# Un_Bus_A.net
KiCad netlist of a schematic drawn in EAGLE
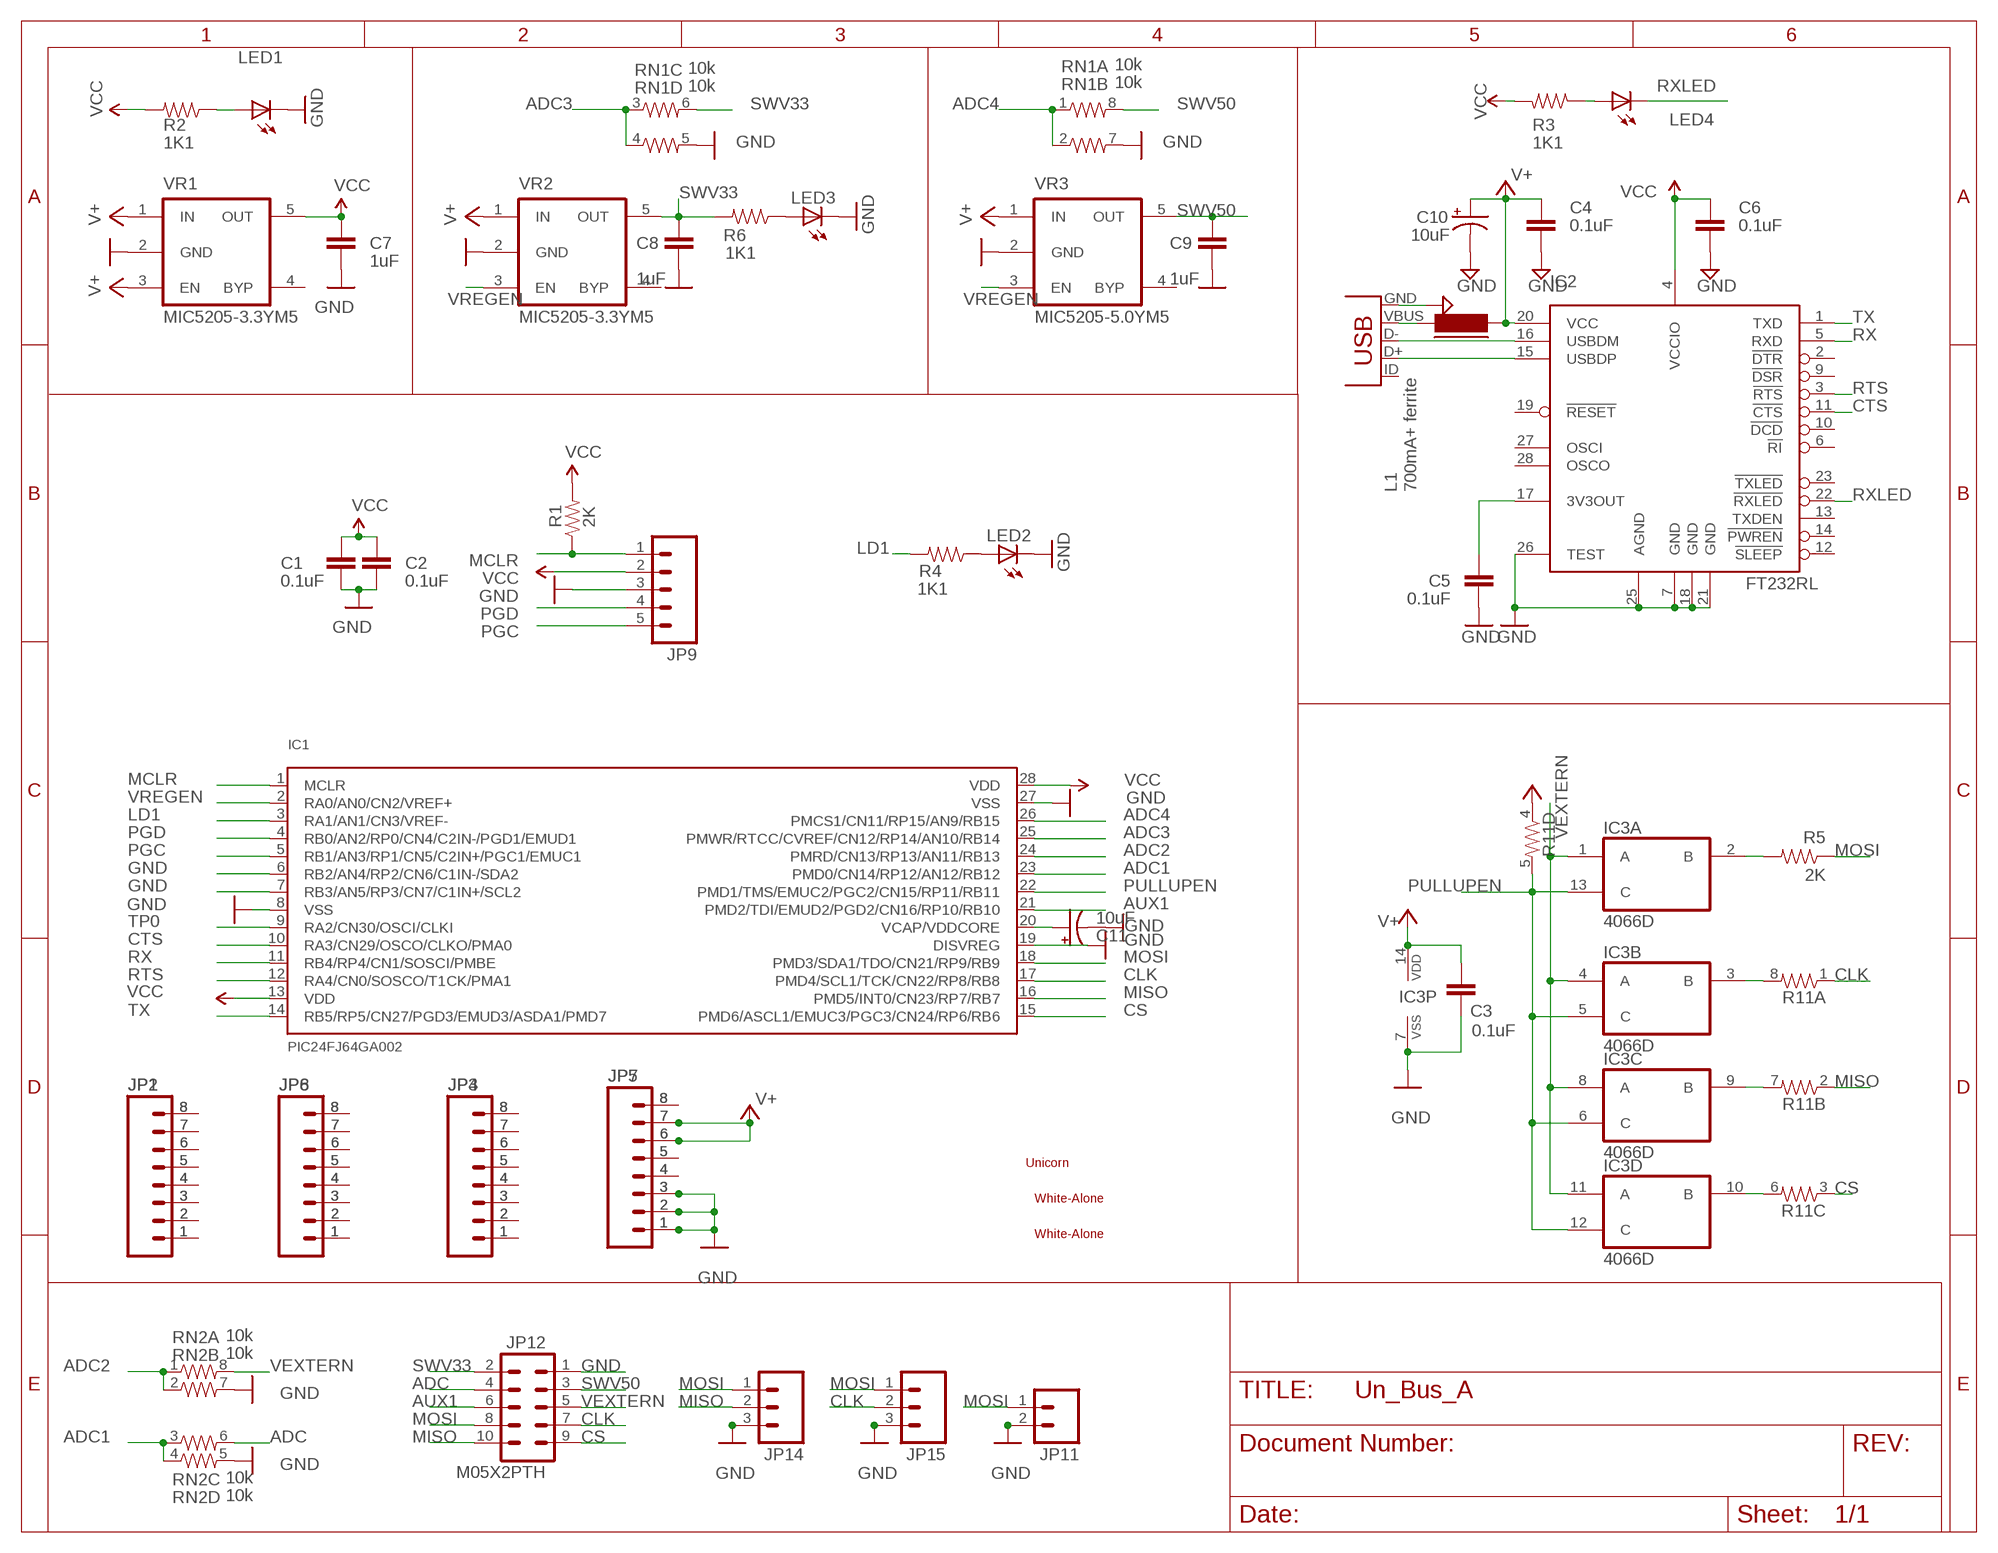
[diagram p0: schematic, sheet 1]

(export (version "E")
  (design (tool "Eeschema 10.0.6"))
  (components
    (comp (ref "C1")
      (value "0.1uF")
      (footprint "eagle-import:0603-CAP")
      (libsource (lib "eagle-import") (part "CAP0603-CAP"))
    )
    (comp (ref "C2")
      (value "0.1uF")
      (footprint "eagle-import:0603-CAP")
      (libsource (lib "eagle-import") (part "CAP0603-CAP"))
    )
    (comp (ref "C3")
      (value "0.1uF")
      (footprint "eagle-import:0603-CAP")
      (libsource (lib "eagle-import") (part "CAP0603-CAP"))
    )
    (comp (ref "C4")
      (value "0.1uF")
      (footprint "eagle-import:0603-CAP")
      (libsource (lib "eagle-import") (part "CAP0603-CAP"))
    )
    (comp (ref "C5")
      (value "0.1uF")
      (footprint "eagle-import:0603-CAP")
      (libsource (lib "eagle-import") (part "CAP0603-CAP"))
    )
    (comp (ref "C6")
      (value "0.1uF")
      (footprint "eagle-import:0603-CAP")
      (libsource (lib "eagle-import") (part "CAP0603-CAP"))
    )
    (comp (ref "C7")
      (value "1uF")
      (footprint "eagle-import:0603-CAP")
      (libsource (lib "eagle-import") (part "CAP0603-CAP"))
    )
    (comp (ref "C8")
      (value "1uF")
      (footprint "eagle-import:0603-CAP")
      (libsource (lib "eagle-import") (part "CAP0603-CAP"))
    )
    (comp (ref "C9")
      (value "1uF")
      (footprint "eagle-import:0603-CAP")
      (libsource (lib "eagle-import") (part "CAP0603-CAP"))
    )
    (comp (ref "C10")
      (value "10uF")
      (footprint "eagle-import:EIA3216")
      (libsource (lib "eagle-import") (part "CAP_POL1206"))
    )
    (comp (ref "C11")
      (value "10uF")
      (footprint "eagle-import:EIA3216")
      (libsource (lib "eagle-import") (part "CAP_POL1206"))
    )
    (comp (ref "IC1")
      (value "PIC24FJ64GA002")
      (footprint "eagle-import:SSOP28")
      (libsource (lib "eagle-import") (part "PIC24FJ64GA002"))
    )
    (comp (ref "IC2")
      (value "FT232RL")
      (footprint "eagle-import:SSOP28")
      (libsource (lib "eagle-import") (part "FT232RL"))
    )
    (comp (ref "IC3")
      (value "4066D")
      (footprint "eagle-import:SO14")
      (libsource (lib "eagle-import") (part "4066D"))
    )
    (comp (ref "JP1")
      (value "M081X08")
      (footprint "eagle-import:1X08")
      (libsource (lib "eagle-import") (part "M081X08"))
    )
    (comp (ref "JP2")
      (value "M081X08")
      (footprint "eagle-import:1X08")
      (libsource (lib "eagle-import") (part "M081X08"))
    )
    (comp (ref "JP3")
      (value "M081X08")
      (footprint "eagle-import:1X08")
      (libsource (lib "eagle-import") (part "M081X08"))
    )
    (comp (ref "JP4")
      (value "M081X08")
      (footprint "eagle-import:1X08")
      (libsource (lib "eagle-import") (part "M081X08"))
    )
    (comp (ref "JP5")
      (value "M081X08")
      (footprint "eagle-import:1X08")
      (libsource (lib "eagle-import") (part "M081X08"))
    )
    (comp (ref "JP6")
      (value "M081X08")
      (footprint "eagle-import:1X08")
      (libsource (lib "eagle-import") (part "M081X08"))
    )
    (comp (ref "JP7")
      (value "M081X08")
      (footprint "eagle-import:1X08")
      (libsource (lib "eagle-import") (part "M081X08"))
    )
    (comp (ref "JP8")
      (value "M081X08")
      (footprint "eagle-import:1X08")
      (libsource (lib "eagle-import") (part "M081X08"))
    )
    (comp (ref "JP9")
      (value "M05PTH")
      (footprint "eagle-import:1X05")
      (libsource (lib "eagle-import") (part "M05PTH"))
    )
    (comp (ref "JP11")
      (value "M02PTH")
      (footprint "eagle-import:1X02")
      (libsource (lib "eagle-import") (part "M02PTH"))
    )
    (comp (ref "JP12")
      (value "M05X2PTH")
      (footprint "eagle-import:AVR_ICSP")
      (libsource (lib "eagle-import") (part "M05X2PTH"))
    )
    (comp (ref "JP14")
      (value "M03PTH")
      (footprint "eagle-import:1X03")
      (libsource (lib "eagle-import") (part "M03PTH"))
    )
    (comp (ref "JP15")
      (value "M03PTH")
      (footprint "eagle-import:1X03")
      (libsource (lib "eagle-import") (part "M03PTH"))
    )
    (comp (ref "L1")
      (value "700mA+ ferrite")
      (footprint "eagle-import:FB805")
      (libsource (lib "eagle-import") (part "FERRITE-0805"))
    )
    (comp (ref "LED1")
      (value "LED0805")
      (footprint "eagle-import:LED-0805")
      (libsource (lib "eagle-import") (part "LED0805"))
    )
    (comp (ref "LED2")
      (value "LED0805")
      (footprint "eagle-import:LED-0805")
      (libsource (lib "eagle-import") (part "LED0805"))
    )
    (comp (ref "LED3")
      (value "LED0805")
      (footprint "eagle-import:LED-0805")
      (libsource (lib "eagle-import") (part "LED0805"))
    )
    (comp (ref "LED4")
      (value "LED0805")
      (footprint "eagle-import:LED-0805")
      (libsource (lib "eagle-import") (part "LED0805"))
    )
    (comp (ref "R1")
      (value "2K")
      (footprint "eagle-import:0603-RES")
      (libsource (lib "eagle-import") (part "2SparkFun_RESISTOR0603-RES"))
    )
    (comp (ref "R2")
      (value "1K1")
      (footprint "eagle-import:0603-RES")
      (libsource (lib "eagle-import") (part "RESISTOR0603-RES"))
    )
    (comp (ref "R3")
      (value "1K1")
      (footprint "eagle-import:0603-RES")
      (libsource (lib "eagle-import") (part "RESISTOR0603-RES"))
    )
    (comp (ref "R4")
      (value "1K1")
      (footprint "eagle-import:0603-RES")
      (libsource (lib "eagle-import") (part "RESISTOR0603-RES"))
    )
    (comp (ref "R5")
      (value "2K")
      (footprint "eagle-import:0603-RES")
      (libsource (lib "eagle-import") (part "2SparkFun_RESISTOR0603-RES"))
    )
    (comp (ref "R6")
      (value "1K1")
      (footprint "eagle-import:0603-RES")
      (libsource (lib "eagle-import") (part "RESISTOR0603-RES"))
    )
    (comp (ref "R11")
      (value "RESISTOR-ARRAY")
      (footprint "eagle-import:RES-NET-0603")
      (libsource (lib "eagle-import") (part "RESISTOR-ARRAY"))
    )
    (comp (ref "RN1")
      (value "10k")
      (footprint "eagle-import:RES-NET-0603")
      (libsource (lib "eagle-import") (part "RESISTOR-ARRAY"))
    )
    (comp (ref "RN2")
      (value "10k")
      (footprint "eagle-import:RES-NET-0603")
      (libsource (lib "eagle-import") (part "RESISTOR-ARRAY"))
    )
    (comp (ref "U$1")
      (value "UNICORN")
      (footprint "eagle-import:UNICORN_1")
      (libsource (lib "eagle-import") (part "UNICORN"))
    )
    (comp (ref "U$2")
      (value "WHITE-ALONE_0")
      (footprint "eagle-import:WHITE-ALONE_0")
      (libsource (lib "eagle-import") (part "WHITE-ALONE_0"))
    )
    (comp (ref "U$3")
      (value "WHITE-ALONE_0")
      (footprint "eagle-import:WHITE-ALONE_0")
      (libsource (lib "eagle-import") (part "WHITE-ALONE_0"))
    )
    (comp (ref "VR1")
      (value "MIC5205-3.3YM5")
      (footprint "eagle-import:SOT-23-5")
      (libsource (lib "eagle-import") (part "MIC5205"))
    )
    (comp (ref "VR2")
      (value "MIC5205-3.3YM5")
      (footprint "eagle-import:SOT-23-5")
      (libsource (lib "eagle-import") (part "MIC5205"))
    )
    (comp (ref "VR3")
      (value "MIC5205-5.0YM5")
      (footprint "eagle-import:SOT-23-5")
      (libsource (lib "eagle-import") (part "MIC5205"))
    )
    (comp (ref "X1")
      (value "USBSMD")
      (footprint "eagle-import:USB-MINIB")
      (libsource (lib "eagle-import") (part "USBSMD"))
    )
  )
  (nets
    (net (code "1") (name "/ADC") (class "Default")
      (node (ref "JP12") (pin "4") (pinfunction "4_4") (pintype "passive"))
      (node (ref "RN2") (pin "6") (pinfunction "2_6") (pintype "passive"))
    )
    (net (code "2") (name "/ADC1") (class "Default")
      (node (ref "IC1") (pin "23") (pinfunction "PMD0/CN14/RP12/AN12/RB12_23") (pintype "bidirectional"))
      (node (ref "RN2") (pin "3") (pinfunction "1_3") (pintype "passive"))
      (node (ref "RN2") (pin "4") (pinfunction "1_4") (pintype "passive"))
    )
    (net (code "3") (name "/ADC2") (class "Default")
      (node (ref "IC1") (pin "24") (pinfunction "PMRD/CN13/RP13/AN11/RB13_24") (pintype "bidirectional"))
      (node (ref "RN2") (pin "1") (pinfunction "1_1") (pintype "passive"))
      (node (ref "RN2") (pin "2") (pinfunction "1_2") (pintype "passive"))
    )
    (net (code "4") (name "/ADC3") (class "Default")
      (node (ref "IC1") (pin "25") (pinfunction "PMWR/RTCC/CVREF/CN12/RP14/AN10/RB14_25") (pintype "bidirectional"))
      (node (ref "RN1") (pin "3") (pinfunction "1_3") (pintype "passive"))
      (node (ref "RN1") (pin "4") (pinfunction "1_4") (pintype "passive"))
    )
    (net (code "5") (name "/ADC4") (class "Default")
      (node (ref "IC1") (pin "26") (pinfunction "PMCS1/CN11/RP15/AN9/RB15_26") (pintype "bidirectional"))
      (node (ref "RN1") (pin "1") (pinfunction "1_1") (pintype "passive"))
      (node (ref "RN1") (pin "2") (pinfunction "1_2") (pintype "passive"))
    )
    (net (code "6") (name "/AUX1") (class "Default")
      (node (ref "IC1") (pin "21") (pinfunction "PMD2/TDI/EMUD2/PGD2/CN16/RP10/RB10_21") (pintype "bidirectional"))
      (node (ref "JP12") (pin "6") (pinfunction "6_6") (pintype "passive"))
    )
    (net (code "7") (name "/CLK") (class "Default")
      (node (ref "IC1") (pin "17") (pinfunction "PMD4/SCL1/TCK/CN22/RP8/RB8_17") (pintype "bidirectional"))
      (node (ref "JP12") (pin "7") (pinfunction "7_7") (pintype "passive"))
      (node (ref "JP15") (pin "2") (pinfunction "2_2") (pintype "passive"))
      (node (ref "R11") (pin "1") (pinfunction "1_1") (pintype "passive"))
    )
    (net (code "8") (name "/CS") (class "Default")
      (node (ref "IC1") (pin "15") (pinfunction "PMD6/ASCL1/EMUC3/PGC3/CN24/RP6/RB6_15") (pintype "bidirectional"))
      (node (ref "JP12") (pin "9") (pinfunction "9_9") (pintype "passive"))
      (node (ref "R11") (pin "3") (pinfunction "1_3") (pintype "passive"))
    )
    (net (code "9") (name "/CTS") (class "Default")
      (node (ref "IC1") (pin "10") (pinfunction "RA3/CN29/OSCO/CLKO/PMA0_10") (pintype "bidirectional"))
      (node (ref "IC2") (pin "11") (pinfunction "~{CTS}_11") (pintype "bidirectional"))
    )
    (net (code "10") (name "/LD1") (class "Default")
      (node (ref "IC1") (pin "3") (pinfunction "RA1/AN1/CN3/VREF-_3") (pintype "bidirectional"))
      (node (ref "R4") (pin "2") (pinfunction "2_2") (pintype "passive"))
    )
    (net (code "11") (name "/MCLR") (class "Default")
      (node (ref "IC1") (pin "1") (pinfunction "MCLR_1") (pintype "input"))
      (node (ref "JP9") (pin "1") (pinfunction "1_1") (pintype "passive"))
      (node (ref "R1") (pin "1") (pinfunction "1_1") (pintype "passive"))
    )
    (net (code "12") (name "/MISO") (class "Default")
      (node (ref "IC1") (pin "16") (pinfunction "PMD5/INT0/CN23/RP7/RB7_16") (pintype "bidirectional"))
      (node (ref "JP12") (pin "10") (pinfunction "10_10") (pintype "passive"))
      (node (ref "JP14") (pin "2") (pinfunction "2_2") (pintype "passive"))
      (node (ref "R11") (pin "2") (pinfunction "1_2") (pintype "passive"))
    )
    (net (code "13") (name "/MOSI") (class "Default")
      (node (ref "IC1") (pin "18") (pinfunction "PMD3/SDA1/TDO/CN21/RP9/RB9_18") (pintype "bidirectional"))
      (node (ref "JP11") (pin "1") (pinfunction "1_1") (pintype "passive"))
      (node (ref "JP12") (pin "8") (pinfunction "8_8") (pintype "passive"))
      (node (ref "JP14") (pin "1") (pinfunction "1_1") (pintype "passive"))
      (node (ref "JP15") (pin "1") (pinfunction "1_1") (pintype "passive"))
      (node (ref "R5") (pin "1") (pinfunction "1_1") (pintype "passive"))
    )
    (net (code "14") (name "/PGC") (class "Default")
      (node (ref "IC1") (pin "5") (pinfunction "RB1/AN3/RP1/CN5/C2IN+/PGC1/EMUC1_5") (pintype "bidirectional"))
      (node (ref "JP9") (pin "5") (pinfunction "5_5") (pintype "passive"))
    )
    (net (code "15") (name "/PGD") (class "Default")
      (node (ref "IC1") (pin "4") (pinfunction "RB0/AN2/RP0/CN4/C2IN-/PGD1/EMUD1_4") (pintype "bidirectional"))
      (node (ref "JP9") (pin "4") (pinfunction "4_4") (pintype "passive"))
    )
    (net (code "16") (name "/PULLUPEN") (class "Default")
      (node (ref "IC1") (pin "22") (pinfunction "PMD1/TMS/EMUC2/PGC2/CN15/RP11/RB11_22") (pintype "bidirectional"))
      (node (ref "IC3") (pin "12") (pinfunction "C_12") (pintype "input"))
      (node (ref "IC3") (pin "13") (pinfunction "C_13") (pintype "input"))
      (node (ref "IC3") (pin "5") (pinfunction "C_5") (pintype "input"))
      (node (ref "IC3") (pin "6") (pinfunction "C_6") (pintype "input"))
      (node (ref "R11") (pin "5") (pinfunction "2_5") (pintype "passive"))
    )
    (net (code "17") (name "/RTS") (class "Default")
      (node (ref "IC1") (pin "12") (pinfunction "RA4/CN0/SOSCO/T1CK/PMA1_12") (pintype "bidirectional"))
      (node (ref "IC2") (pin "3") (pinfunction "~{RTS}_3") (pintype "bidirectional"))
    )
    (net (code "18") (name "/RX") (class "Default")
      (node (ref "IC1") (pin "11") (pinfunction "RB4/RP4/CN1/SOSCI/PMBE_11") (pintype "bidirectional"))
      (node (ref "IC2") (pin "5") (pinfunction "RXD_5") (pintype "bidirectional"))
    )
    (net (code "19") (name "/RXLED") (class "Default")
      (node (ref "IC2") (pin "22") (pinfunction "~{RXLED}_22") (pintype "bidirectional"))
      (node (ref "LED4") (pin "2") (pinfunction "C_2") (pintype "passive"))
    )
    (net (code "20") (name "/SWV33") (class "Default")
      (node (ref "C8") (pin "1") (pinfunction "1_1") (pintype "passive"))
      (node (ref "JP12") (pin "2") (pinfunction "2_2") (pintype "passive"))
      (node (ref "R6") (pin "2") (pinfunction "2_2") (pintype "passive"))
      (node (ref "RN1") (pin "6") (pinfunction "2_6") (pintype "passive"))
      (node (ref "VR2") (pin "5") (pinfunction "OUT_5") (pintype "bidirectional"))
    )
    (net (code "21") (name "/SWV50") (class "Default")
      (node (ref "C9") (pin "1") (pinfunction "1_1") (pintype "passive"))
      (node (ref "JP12") (pin "3") (pinfunction "3_3") (pintype "passive"))
      (node (ref "RN1") (pin "8") (pinfunction "2_8") (pintype "passive"))
      (node (ref "VR3") (pin "5") (pinfunction "OUT_5") (pintype "bidirectional"))
    )
    (net (code "22") (name "/TP0") (class "Default")
      (node (ref "IC1") (pin "9") (pinfunction "RA2/CN30/OSCI/CLKI_9") (pintype "bidirectional"))
    )
    (net (code "23") (name "/TX") (class "Default")
      (node (ref "IC1") (pin "14") (pinfunction "RB5/RP5/CN27/PGD3/EMUD3/ASDA1/PMD7_14") (pintype "bidirectional"))
      (node (ref "IC2") (pin "1") (pinfunction "TXD_1") (pintype "bidirectional"))
    )
    (net (code "24") (name "/VEXTERN") (class "Default")
      (node (ref "IC3") (pin "1") (pinfunction "A_1") (pintype "tri_state"))
      (node (ref "IC3") (pin "11") (pinfunction "A_11") (pintype "tri_state"))
      (node (ref "IC3") (pin "4") (pinfunction "A_4") (pintype "tri_state"))
      (node (ref "IC3") (pin "8") (pinfunction "A_8") (pintype "tri_state"))
      (node (ref "JP12") (pin "5") (pinfunction "5_5") (pintype "passive"))
      (node (ref "RN2") (pin "8") (pinfunction "2_8") (pintype "passive"))
    )
    (net (code "25") (name "/VREGEN") (class "Default")
      (node (ref "IC1") (pin "2") (pinfunction "RA0/AN0/CN2/VREF+_2") (pintype "bidirectional"))
      (node (ref "VR2") (pin "3") (pinfunction "EN_3") (pintype "bidirectional"))
      (node (ref "VR3") (pin "3") (pinfunction "EN_3") (pintype "bidirectional"))
    )
    (net (code "26") (name "GND") (class "Default")
      (node (ref "C1") (pin "2") (pinfunction "2_2") (pintype "passive"))
      (node (ref "C10") (pin "C") (pinfunction "-_C") (pintype "passive"))
      (node (ref "C11") (pin "C") (pinfunction "-_C") (pintype "passive"))
      (node (ref "C2") (pin "2") (pinfunction "2_2") (pintype "passive"))
      (node (ref "C3") (pin "2") (pinfunction "2_2") (pintype "passive"))
      (node (ref "C4") (pin "2") (pinfunction "2_2") (pintype "passive"))
      (node (ref "C5") (pin "2") (pinfunction "2_2") (pintype "passive"))
      (node (ref "C6") (pin "2") (pinfunction "2_2") (pintype "passive"))
      (node (ref "C7") (pin "2") (pinfunction "2_2") (pintype "passive"))
      (node (ref "C8") (pin "2") (pinfunction "2_2") (pintype "passive"))
      (node (ref "C9") (pin "2") (pinfunction "2_2") (pintype "passive"))
      (node (ref "IC1") (pin "19") (pinfunction "DISVREG_19") (pintype "power_in"))
      (node (ref "IC1") (pin "27") (pinfunction "VSS_27") (pintype "power_in"))
      (node (ref "IC1") (pin "6") (pinfunction "RB2/AN4/RP2/CN6/C1IN-/SDA2_6") (pintype "bidirectional"))
      (node (ref "IC1") (pin "7") (pinfunction "RB3/AN5/RP3/CN7/C1IN+/SCL2_7") (pintype "bidirectional"))
      (node (ref "IC1") (pin "8") (pinfunction "VSS_8") (pintype "power_in"))
      (node (ref "IC2") (pin "18") (pinfunction "GND_18") (pintype "bidirectional"))
      (node (ref "IC2") (pin "21") (pinfunction "GND_21") (pintype "bidirectional"))
      (node (ref "IC2") (pin "25") (pinfunction "AGND_25") (pintype "bidirectional"))
      (node (ref "IC2") (pin "26") (pinfunction "TEST_26") (pintype "bidirectional"))
      (node (ref "IC2") (pin "7") (pinfunction "GND_7") (pintype "bidirectional"))
      (node (ref "IC3") (pin "7") (pinfunction "VSS_7") (pintype "power_in"))
      (node (ref "JP11") (pin "2") (pinfunction "2_2") (pintype "passive"))
      (node (ref "JP12") (pin "1") (pinfunction "1_1") (pintype "passive"))
      (node (ref "JP14") (pin "3") (pinfunction "3_3") (pintype "passive"))
      (node (ref "JP15") (pin "3") (pinfunction "3_3") (pintype "passive"))
      (node (ref "JP5") (pin "1") (pinfunction "1_1") (pintype "passive"))
      (node (ref "JP5") (pin "2") (pinfunction "2_2") (pintype "passive"))
      (node (ref "JP5") (pin "3") (pinfunction "3_3") (pintype "passive"))
      (node (ref "JP7") (pin "1") (pinfunction "1_1") (pintype "passive"))
      (node (ref "JP7") (pin "2") (pinfunction "2_2") (pintype "passive"))
      (node (ref "JP7") (pin "3") (pinfunction "3_3") (pintype "passive"))
      (node (ref "JP9") (pin "3") (pinfunction "3_3") (pintype "passive"))
      (node (ref "LED1") (pin "2") (pinfunction "C_2") (pintype "passive"))
      (node (ref "LED2") (pin "2") (pinfunction "C_2") (pintype "passive"))
      (node (ref "LED3") (pin "2") (pinfunction "C_2") (pintype "passive"))
      (node (ref "RN1") (pin "5") (pinfunction "2_5") (pintype "passive"))
      (node (ref "RN1") (pin "7") (pinfunction "2_7") (pintype "passive"))
      (node (ref "RN2") (pin "5") (pinfunction "2_5") (pintype "passive"))
      (node (ref "RN2") (pin "7") (pinfunction "2_7") (pintype "passive"))
      (node (ref "VR1") (pin "2") (pinfunction "GND_2") (pintype "bidirectional"))
      (node (ref "VR2") (pin "2") (pinfunction "GND_2") (pintype "bidirectional"))
      (node (ref "VR3") (pin "2") (pinfunction "GND_2") (pintype "bidirectional"))
      (node (ref "X1") (pin "GND") (pinfunction "GND_GND") (pintype "bidirectional"))
    )
    (net (code "27") (name "Net-(C11-+)") (class "Default")
      (node (ref "C11") (pin "A") (pinfunction "+_A") (pintype "passive"))
      (node (ref "IC1") (pin "20") (pinfunction "VCAP/VDDCORE_20") (pintype "power_in"))
    )
    (net (code "28") (name "Net-(IC2-3V3OUT)") (class "Default")
      (node (ref "C5") (pin "1") (pinfunction "1_1") (pintype "passive"))
      (node (ref "IC2") (pin "17") (pinfunction "3V3OUT_17") (pintype "bidirectional"))
    )
    (net (code "29") (name "Net-(IC2-USBDM)") (class "Default")
      (node (ref "IC2") (pin "16") (pinfunction "USBDM_16") (pintype "bidirectional"))
      (node (ref "X1") (pin "D-") (pinfunction "D-_D-") (pintype "bidirectional"))
    )
    (net (code "30") (name "Net-(IC2-USBDP)") (class "Default")
      (node (ref "IC2") (pin "15") (pinfunction "USBDP_15") (pintype "bidirectional"))
      (node (ref "X1") (pin "D+") (pinfunction "D+_D+") (pintype "bidirectional"))
    )
    (net (code "31") (name "Net-(IC3A-B)") (class "Default")
      (node (ref "IC3") (pin "2") (pinfunction "B_2") (pintype "tri_state"))
      (node (ref "R5") (pin "2") (pinfunction "2_2") (pintype "passive"))
    )
    (net (code "32") (name "Net-(IC3B-B)") (class "Default")
      (node (ref "IC3") (pin "3") (pinfunction "B_3") (pintype "tri_state"))
      (node (ref "R11") (pin "8") (pinfunction "2_8") (pintype "passive"))
    )
    (net (code "33") (name "Net-(IC3C-B)") (class "Default")
      (node (ref "IC3") (pin "9") (pinfunction "B_9") (pintype "tri_state"))
      (node (ref "R11") (pin "7") (pinfunction "2_7") (pintype "passive"))
    )
    (net (code "34") (name "Net-(IC3D-B)") (class "Default")
      (node (ref "IC3") (pin "10") (pinfunction "B_10") (pintype "tri_state"))
      (node (ref "R11") (pin "6") (pinfunction "2_6") (pintype "passive"))
    )
    (net (code "35") (name "Net-(JP1-Pad1)") (class "Default")
      (node (ref "JP1") (pin "1") (pinfunction "1_1") (pintype "passive"))
      (node (ref "JP2") (pin "1") (pinfunction "1_1") (pintype "passive"))
    )
    (net (code "36") (name "Net-(JP1-Pad2)") (class "Default")
      (node (ref "JP1") (pin "2") (pinfunction "2_2") (pintype "passive"))
      (node (ref "JP2") (pin "2") (pinfunction "2_2") (pintype "passive"))
    )
    (net (code "37") (name "Net-(JP1-Pad3)") (class "Default")
      (node (ref "JP1") (pin "3") (pinfunction "3_3") (pintype "passive"))
      (node (ref "JP2") (pin "3") (pinfunction "3_3") (pintype "passive"))
    )
    (net (code "38") (name "Net-(JP1-Pad4)") (class "Default")
      (node (ref "JP1") (pin "4") (pinfunction "4_4") (pintype "passive"))
      (node (ref "JP2") (pin "4") (pinfunction "4_4") (pintype "passive"))
    )
    (net (code "39") (name "Net-(JP1-Pad5)") (class "Default")
      (node (ref "JP1") (pin "5") (pinfunction "5_5") (pintype "passive"))
      (node (ref "JP2") (pin "5") (pinfunction "5_5") (pintype "passive"))
    )
    (net (code "40") (name "Net-(JP1-Pad6)") (class "Default")
      (node (ref "JP1") (pin "6") (pinfunction "6_6") (pintype "passive"))
      (node (ref "JP2") (pin "6") (pinfunction "6_6") (pintype "passive"))
    )
    (net (code "41") (name "Net-(JP1-Pad7)") (class "Default")
      (node (ref "JP1") (pin "7") (pinfunction "7_7") (pintype "passive"))
      (node (ref "JP2") (pin "7") (pinfunction "7_7") (pintype "passive"))
    )
    (net (code "42") (name "Net-(JP1-Pad8)") (class "Default")
      (node (ref "JP1") (pin "8") (pinfunction "8_8") (pintype "passive"))
      (node (ref "JP2") (pin "8") (pinfunction "8_8") (pintype "passive"))
    )
    (net (code "43") (name "Net-(JP3-Pad1)") (class "Default")
      (node (ref "JP3") (pin "1") (pinfunction "1_1") (pintype "passive"))
      (node (ref "JP4") (pin "1") (pinfunction "1_1") (pintype "passive"))
    )
    (net (code "44") (name "Net-(JP3-Pad2)") (class "Default")
      (node (ref "JP3") (pin "2") (pinfunction "2_2") (pintype "passive"))
      (node (ref "JP4") (pin "2") (pinfunction "2_2") (pintype "passive"))
    )
    (net (code "45") (name "Net-(JP3-Pad3)") (class "Default")
      (node (ref "JP3") (pin "3") (pinfunction "3_3") (pintype "passive"))
      (node (ref "JP4") (pin "3") (pinfunction "3_3") (pintype "passive"))
    )
    (net (code "46") (name "Net-(JP3-Pad4)") (class "Default")
      (node (ref "JP3") (pin "4") (pinfunction "4_4") (pintype "passive"))
      (node (ref "JP4") (pin "4") (pinfunction "4_4") (pintype "passive"))
    )
    (net (code "47") (name "Net-(JP3-Pad5)") (class "Default")
      (node (ref "JP3") (pin "5") (pinfunction "5_5") (pintype "passive"))
      (node (ref "JP4") (pin "5") (pinfunction "5_5") (pintype "passive"))
    )
    (net (code "48") (name "Net-(JP3-Pad6)") (class "Default")
      (node (ref "JP3") (pin "6") (pinfunction "6_6") (pintype "passive"))
      (node (ref "JP4") (pin "6") (pinfunction "6_6") (pintype "passive"))
    )
    (net (code "49") (name "Net-(JP3-Pad7)") (class "Default")
      (node (ref "JP3") (pin "7") (pinfunction "7_7") (pintype "passive"))
      (node (ref "JP4") (pin "7") (pinfunction "7_7") (pintype "passive"))
    )
    (net (code "50") (name "Net-(JP3-Pad8)") (class "Default")
      (node (ref "JP3") (pin "8") (pinfunction "8_8") (pintype "passive"))
      (node (ref "JP4") (pin "8") (pinfunction "8_8") (pintype "passive"))
    )
    (net (code "51") (name "Net-(JP5-Pad4)") (class "Default")
      (node (ref "JP5") (pin "4") (pinfunction "4_4") (pintype "passive"))
      (node (ref "JP7") (pin "4") (pinfunction "4_4") (pintype "passive"))
    )
    (net (code "52") (name "Net-(JP5-Pad5)") (class "Default")
      (node (ref "JP5") (pin "5") (pinfunction "5_5") (pintype "passive"))
      (node (ref "JP7") (pin "5") (pinfunction "5_5") (pintype "passive"))
    )
    (net (code "53") (name "Net-(JP5-Pad8)") (class "Default")
      (node (ref "JP5") (pin "8") (pinfunction "8_8") (pintype "passive"))
      (node (ref "JP7") (pin "8") (pinfunction "8_8") (pintype "passive"))
    )
    (net (code "54") (name "Net-(JP6-Pad1)") (class "Default")
      (node (ref "JP6") (pin "1") (pinfunction "1_1") (pintype "passive"))
      (node (ref "JP8") (pin "1") (pinfunction "1_1") (pintype "passive"))
    )
    (net (code "55") (name "Net-(JP6-Pad2)") (class "Default")
      (node (ref "JP6") (pin "2") (pinfunction "2_2") (pintype "passive"))
      (node (ref "JP8") (pin "2") (pinfunction "2_2") (pintype "passive"))
    )
    (net (code "56") (name "Net-(JP6-Pad3)") (class "Default")
      (node (ref "JP6") (pin "3") (pinfunction "3_3") (pintype "passive"))
      (node (ref "JP8") (pin "3") (pinfunction "3_3") (pintype "passive"))
    )
    (net (code "57") (name "Net-(JP6-Pad4)") (class "Default")
      (node (ref "JP6") (pin "4") (pinfunction "4_4") (pintype "passive"))
      (node (ref "JP8") (pin "4") (pinfunction "4_4") (pintype "passive"))
    )
    (net (code "58") (name "Net-(JP6-Pad5)") (class "Default")
      (node (ref "JP6") (pin "5") (pinfunction "5_5") (pintype "passive"))
      (node (ref "JP8") (pin "5") (pinfunction "5_5") (pintype "passive"))
    )
    (net (code "59") (name "Net-(JP6-Pad6)") (class "Default")
      (node (ref "JP6") (pin "6") (pinfunction "6_6") (pintype "passive"))
      (node (ref "JP8") (pin "6") (pinfunction "6_6") (pintype "passive"))
    )
    (net (code "60") (name "Net-(JP6-Pad7)") (class "Default")
      (node (ref "JP6") (pin "7") (pinfunction "7_7") (pintype "passive"))
      (node (ref "JP8") (pin "7") (pinfunction "7_7") (pintype "passive"))
    )
    (net (code "61") (name "Net-(JP6-Pad8)") (class "Default")
      (node (ref "JP6") (pin "8") (pinfunction "8_8") (pintype "passive"))
      (node (ref "JP8") (pin "8") (pinfunction "8_8") (pintype "passive"))
    )
    (net (code "62") (name "Net-(L1-Pad1)") (class "Default")
      (node (ref "L1") (pin "1") (pinfunction "1_1") (pintype "passive"))
      (node (ref "X1") (pin "VBUS") (pinfunction "VBUS_VBUS") (pintype "bidirectional"))
    )
    (net (code "63") (name "Net-(LED1-A)") (class "Default")
      (node (ref "LED1") (pin "1") (pinfunction "A_1") (pintype "passive"))
      (node (ref "R2") (pin "1") (pinfunction "1_1") (pintype "passive"))
    )
    (net (code "64") (name "Net-(LED2-A)") (class "Default")
      (node (ref "LED2") (pin "1") (pinfunction "A_1") (pintype "passive"))
      (node (ref "R4") (pin "1") (pinfunction "1_1") (pintype "passive"))
    )
    (net (code "65") (name "Net-(LED3-A)") (class "Default")
      (node (ref "LED3") (pin "1") (pinfunction "A_1") (pintype "passive"))
      (node (ref "R6") (pin "1") (pinfunction "1_1") (pintype "passive"))
    )
    (net (code "66") (name "Net-(LED4-A)") (class "Default")
      (node (ref "LED4") (pin "1") (pinfunction "A_1") (pintype "passive"))
      (node (ref "R3") (pin "1") (pinfunction "1_1") (pintype "passive"))
    )
    (net (code "67") (name "V+") (class "Default")
      (node (ref "C10") (pin "A") (pinfunction "+_A") (pintype "passive"))
      (node (ref "C3") (pin "1") (pinfunction "1_1") (pintype "passive"))
      (node (ref "C4") (pin "1") (pinfunction "1_1") (pintype "passive"))
      (node (ref "IC2") (pin "20") (pinfunction "VCC_20") (pintype "bidirectional"))
      (node (ref "IC3") (pin "14") (pinfunction "VDD_14") (pintype "power_in"))
      (node (ref "JP5") (pin "6") (pinfunction "6_6") (pintype "passive"))
      (node (ref "JP5") (pin "7") (pinfunction "7_7") (pintype "passive"))
      (node (ref "JP7") (pin "6") (pinfunction "6_6") (pintype "passive"))
      (node (ref "JP7") (pin "7") (pinfunction "7_7") (pintype "passive"))
      (node (ref "L1") (pin "2") (pinfunction "2_2") (pintype "passive"))
      (node (ref "R11") (pin "4") (pinfunction "1_4") (pintype "passive"))
      (node (ref "VR1") (pin "1") (pinfunction "IN_1") (pintype "bidirectional"))
      (node (ref "VR1") (pin "3") (pinfunction "EN_3") (pintype "bidirectional"))
      (node (ref "VR2") (pin "1") (pinfunction "IN_1") (pintype "bidirectional"))
      (node (ref "VR3") (pin "1") (pinfunction "IN_1") (pintype "bidirectional"))
    )
    (net (code "68") (name "VCC") (class "Default")
      (node (ref "C1") (pin "1") (pinfunction "1_1") (pintype "passive"))
      (node (ref "C2") (pin "1") (pinfunction "1_1") (pintype "passive"))
      (node (ref "C6") (pin "1") (pinfunction "1_1") (pintype "passive"))
      (node (ref "C7") (pin "1") (pinfunction "1_1") (pintype "passive"))
      (node (ref "IC1") (pin "13") (pinfunction "VDD_13") (pintype "power_in"))
      (node (ref "IC1") (pin "28") (pinfunction "VDD_28") (pintype "power_in"))
      (node (ref "IC2") (pin "4") (pinfunction "VCCIO_4") (pintype "bidirectional"))
      (node (ref "JP9") (pin "2") (pinfunction "2_2") (pintype "passive"))
      (node (ref "R1") (pin "2") (pinfunction "2_2") (pintype "passive"))
      (node (ref "R2") (pin "2") (pinfunction "2_2") (pintype "passive"))
      (node (ref "R3") (pin "2") (pinfunction "2_2") (pintype "passive"))
      (node (ref "VR1") (pin "5") (pinfunction "OUT_5") (pintype "bidirectional"))
    )
    (net (code "69") (name "unconnected-(IC2-OSCI-Pad27)") (class "Default")
      (node (ref "IC2") (pin "27") (pinfunction "OSCI_27") (pintype "bidirectional"))
    )
    (net (code "70") (name "unconnected-(IC2-OSCO-Pad28)") (class "Default")
      (node (ref "IC2") (pin "28") (pinfunction "OSCO_28") (pintype "bidirectional"))
    )
    (net (code "71") (name "unconnected-(IC2-TXDEN-Pad13)") (class "Default")
      (node (ref "IC2") (pin "13") (pinfunction "TXDEN_13") (pintype "bidirectional"))
    )
    (net (code "72") (name "unconnected-(IC2-~{DCD}-Pad10)") (class "Default")
      (node (ref "IC2") (pin "10") (pinfunction "~{DCD}_10") (pintype "bidirectional"))
    )
    (net (code "73") (name "unconnected-(IC2-~{DSR}-Pad9)") (class "Default")
      (node (ref "IC2") (pin "9") (pinfunction "~{DSR}_9") (pintype "bidirectional"))
    )
    (net (code "74") (name "unconnected-(IC2-~{DTR}-Pad2)") (class "Default")
      (node (ref "IC2") (pin "2") (pinfunction "~{DTR}_2") (pintype "bidirectional"))
    )
    (net (code "75") (name "unconnected-(IC2-~{PWREN}-Pad14)") (class "Default")
      (node (ref "IC2") (pin "14") (pinfunction "~{PWREN}_14") (pintype "bidirectional"))
    )
    (net (code "76") (name "unconnected-(IC2-~{RESET}-Pad19)") (class "Default")
      (node (ref "IC2") (pin "19") (pinfunction "~{RESET}_19") (pintype "bidirectional"))
    )
    (net (code "77") (name "unconnected-(IC2-~{RI}-Pad6)") (class "Default")
      (node (ref "IC2") (pin "6") (pinfunction "~{RI}_6") (pintype "bidirectional"))
    )
    (net (code "78") (name "unconnected-(IC2-~{SLEEP}-Pad12)") (class "Default")
      (node (ref "IC2") (pin "12") (pinfunction "~{SLEEP}_12") (pintype "bidirectional"))
    )
    (net (code "79") (name "unconnected-(IC2-~{TXLED}-Pad23)") (class "Default")
      (node (ref "IC2") (pin "23") (pinfunction "~{TXLED}_23") (pintype "bidirectional"))
    )
    (net (code "80") (name "unconnected-(VR1-BYP-Pad4)") (class "Default")
      (node (ref "VR1") (pin "4") (pinfunction "BYP_4") (pintype "bidirectional"))
    )
    (net (code "81") (name "unconnected-(VR2-BYP-Pad4)") (class "Default")
      (node (ref "VR2") (pin "4") (pinfunction "BYP_4") (pintype "bidirectional"))
    )
    (net (code "82") (name "unconnected-(VR3-BYP-Pad4)") (class "Default")
      (node (ref "VR3") (pin "4") (pinfunction "BYP_4") (pintype "bidirectional"))
    )
    (net (code "83") (name "unconnected-(X1-USBID-PadID)") (class "Default")
      (node (ref "X1") (pin "ID") (pinfunction "USBID_ID") (pintype "bidirectional"))
    )
  )
)
